# QCopterMV_MCU_Sch.net
KiCad netlist of a schematic drawn in Altium Designer
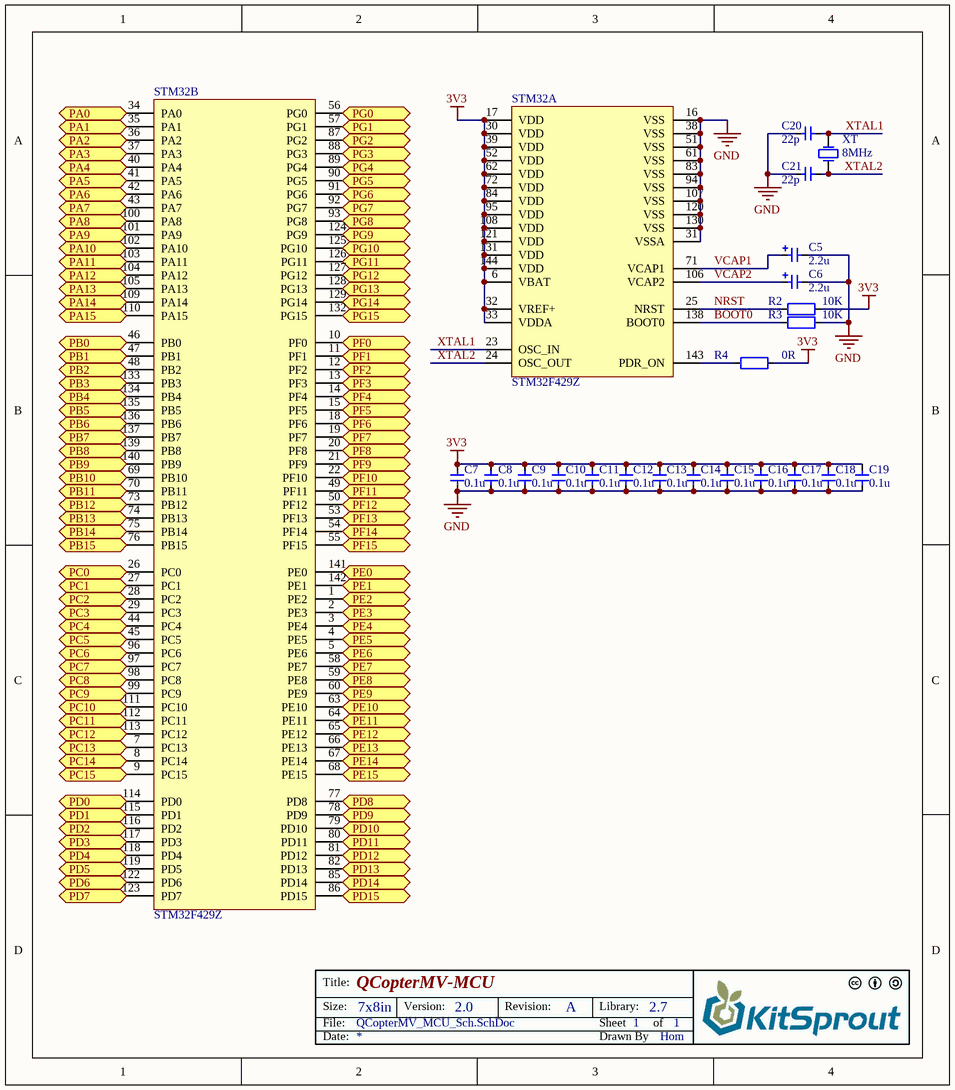
[diagram p0: QCopterMV_MCU_Sch.SchDoc]

(export (version "E")
  (design (tool "Eeschema 10.0.6"))
  (components
    (comp (ref "C5")
      (value "2.2u")
      (footprint "PCB_PassiveCap:CAP_TAN_P0805")
      (description "Capacitor")
      (fields (field (name "Comment") "Cap_Tan_0805"))
      (libsource (lib "SCH_Passive") (part "Cap_Tan_0805"))
    )
    (comp (ref "C6")
      (value "2.2u")
      (footprint "PCB_PassiveCap:CAP_TAN_P0805")
      (description "Capacitor")
      (fields (field (name "Comment") "Cap_Tan_0805"))
      (libsource (lib "SCH_Passive") (part "Cap_Tan_0805"))
    )
    (comp (ref "C7")
      (value "0.1u")
      (footprint "PCB_PassiveCap:CAP_0402")
      (description "Capacitor")
      (fields (field (name "Comment") "Cap_0402"))
      (libsource (lib "SCH_Passive") (part "Cap_0402"))
    )
    (comp (ref "C8")
      (value "0.1u")
      (footprint "PCB_PassiveCap:CAP_0402")
      (description "Capacitor")
      (fields (field (name "Comment") "Cap_0402"))
      (libsource (lib "SCH_Passive") (part "Cap_0402"))
    )
    (comp (ref "C9")
      (value "0.1u")
      (footprint "PCB_PassiveCap:CAP_0402")
      (description "Capacitor")
      (fields (field (name "Comment") "Cap_0402"))
      (libsource (lib "SCH_Passive") (part "Cap_0402"))
    )
    (comp (ref "C10")
      (value "0.1u")
      (footprint "PCB_PassiveCap:CAP_0402")
      (description "Capacitor")
      (fields (field (name "Comment") "Cap_0402"))
      (libsource (lib "SCH_Passive") (part "Cap_0402"))
    )
    (comp (ref "C11")
      (value "0.1u")
      (footprint "PCB_PassiveCap:CAP_0402")
      (description "Capacitor")
      (fields (field (name "Comment") "Cap_0402"))
      (libsource (lib "SCH_Passive") (part "Cap_0402"))
    )
    (comp (ref "C12")
      (value "0.1u")
      (footprint "PCB_PassiveCap:CAP_0402")
      (description "Capacitor")
      (fields (field (name "Comment") "Cap_0402"))
      (libsource (lib "SCH_Passive") (part "Cap_0402"))
    )
    (comp (ref "C13")
      (value "0.1u")
      (footprint "PCB_PassiveCap:CAP_0402")
      (description "Capacitor")
      (fields (field (name "Comment") "Cap_0402"))
      (libsource (lib "SCH_Passive") (part "Cap_0402"))
    )
    (comp (ref "C14")
      (value "0.1u")
      (footprint "PCB_PassiveCap:CAP_0402")
      (description "Capacitor")
      (fields (field (name "Comment") "Cap_0402"))
      (libsource (lib "SCH_Passive") (part "Cap_0402"))
    )
    (comp (ref "C15")
      (value "0.1u")
      (footprint "PCB_PassiveCap:CAP_0402")
      (description "Capacitor")
      (fields (field (name "Comment") "Cap_0402"))
      (libsource (lib "SCH_Passive") (part "Cap_0402"))
    )
    (comp (ref "C16")
      (value "0.1u")
      (footprint "PCB_PassiveCap:CAP_0402")
      (description "Capacitor")
      (fields (field (name "Comment") "Cap_0402"))
      (libsource (lib "SCH_Passive") (part "Cap_0402"))
    )
    (comp (ref "C17")
      (value "0.1u")
      (footprint "PCB_PassiveCap:CAP_0402")
      (description "Capacitor")
      (fields (field (name "Comment") "Cap_0402"))
      (libsource (lib "SCH_Passive") (part "Cap_0402"))
    )
    (comp (ref "C18")
      (value "0.1u")
      (footprint "PCB_PassiveCap:CAP_0402")
      (description "Capacitor")
      (fields (field (name "Comment") "Cap_0402"))
      (libsource (lib "SCH_Passive") (part "Cap_0402"))
    )
    (comp (ref "C19")
      (value "0.1u")
      (footprint "PCB_PassiveCap:CAP_0402")
      (description "Capacitor")
      (fields (field (name "Comment") "Cap_0402"))
      (libsource (lib "SCH_Passive") (part "Cap_0402"))
    )
    (comp (ref "C20")
      (value "22p")
      (footprint "PCB_PassiveCap:CAP_0402")
      (description "Capacitor")
      (fields (field (name "Comment") "Cap_0402"))
      (libsource (lib "SCH_Passive") (part "Cap_0402"))
    )
    (comp (ref "C21")
      (value "22p")
      (footprint "PCB_PassiveCap:CAP_0402")
      (description "Capacitor")
      (fields (field (name "Comment") "Cap_0402"))
      (libsource (lib "SCH_Passive") (part "Cap_0402"))
    )
    (comp (ref "R2")
      (value "10K")
      (footprint "PCB_PassiveRes:RES_0402")
      (description "Resistor")
      (fields (field (name "Comment") "Res_0402"))
      (libsource (lib "SCH_Passive") (part "Res_0402"))
    )
    (comp (ref "R3")
      (value "10K")
      (footprint "PCB_PassiveRes:RES_0402")
      (description "Resistor")
      (fields (field (name "Comment") "Res_0402"))
      (libsource (lib "SCH_Passive") (part "Res_0402"))
    )
    (comp (ref "R4")
      (value "0R")
      (footprint "PCB_PassiveRes:RES_0402")
      (description "Resistor")
      (fields (field (name "Comment") "Res_0402"))
      (libsource (lib "SCH_Passive") (part "Res_0402"))
    )
    (comp (ref "STM32")
      (value "STM32F429Z")
      (footprint "PCB_IntegratedCircuit:LQFP_P0.5_144")
      (description "MCU")
      (libsource (lib "SCH_IntegratedCircuit") (part "STM32F439Z"))
    )
    (comp (ref "XT")
      (value "8MHz")
      (footprint "PCB_Oscillator:XT_3225_2")
      (description "Crystal Oscillator")
      (fields (field (name "Comment") "XTAL_3225_2P"))
      (libsource (lib "SCH_Oscillator") (part "XTAL_3225_2P"))
    )
  )
  (nets
    (net (code "1") (name "/BOOT0") (class "Default")
      (node (ref "R3") (pin "2") (pinfunction "2_2") (pintype "passive"))
      (node (ref "STM32") (pin "138") (pinfunction "BOOT0_138") (pintype "passive"))
    )
    (net (code "2") (name "/NRST") (class "Default")
      (node (ref "R2") (pin "2") (pinfunction "2_2") (pintype "passive"))
      (node (ref "STM32") (pin "25") (pinfunction "NRST_25") (pintype "passive"))
    )
    (net (code "3") (name "/PA0") (class "Default")
      (node (ref "STM32") (pin "34") (pinfunction "PA0_34") (pintype "passive"))
    )
    (net (code "4") (name "/PA1") (class "Default")
      (node (ref "STM32") (pin "35") (pinfunction "PA1_35") (pintype "passive"))
    )
    (net (code "5") (name "/PA2") (class "Default")
      (node (ref "STM32") (pin "36") (pinfunction "PA2_36") (pintype "passive"))
    )
    (net (code "6") (name "/PA3") (class "Default")
      (node (ref "STM32") (pin "37") (pinfunction "PA3_37") (pintype "passive"))
    )
    (net (code "7") (name "/PA4") (class "Default")
      (node (ref "STM32") (pin "40") (pinfunction "PA4_40") (pintype "passive"))
    )
    (net (code "8") (name "/PA5") (class "Default")
      (node (ref "STM32") (pin "41") (pinfunction "PA5_41") (pintype "passive"))
    )
    (net (code "9") (name "/PA6") (class "Default")
      (node (ref "STM32") (pin "42") (pinfunction "PA6_42") (pintype "passive"))
    )
    (net (code "10") (name "/PA7") (class "Default")
      (node (ref "STM32") (pin "43") (pinfunction "PA7_43") (pintype "passive"))
    )
    (net (code "11") (name "/PA8") (class "Default")
      (node (ref "STM32") (pin "100") (pinfunction "PA8_100") (pintype "passive"))
    )
    (net (code "12") (name "/PA9") (class "Default")
      (node (ref "STM32") (pin "101") (pinfunction "PA9_101") (pintype "passive"))
    )
    (net (code "13") (name "/PA10") (class "Default")
      (node (ref "STM32") (pin "102") (pinfunction "PA10_102") (pintype "passive"))
    )
    (net (code "14") (name "/PA11") (class "Default")
      (node (ref "STM32") (pin "103") (pinfunction "PA11_103") (pintype "passive"))
    )
    (net (code "15") (name "/PA12") (class "Default")
      (node (ref "STM32") (pin "104") (pinfunction "PA12_104") (pintype "passive"))
    )
    (net (code "16") (name "/PA13") (class "Default")
      (node (ref "STM32") (pin "105") (pinfunction "PA13_105") (pintype "passive"))
    )
    (net (code "17") (name "/PA14") (class "Default")
      (node (ref "STM32") (pin "109") (pinfunction "PA14_109") (pintype "passive"))
    )
    (net (code "18") (name "/PA15") (class "Default")
      (node (ref "STM32") (pin "110") (pinfunction "PA15_110") (pintype "passive"))
    )
    (net (code "19") (name "/PB0") (class "Default")
      (node (ref "STM32") (pin "46") (pinfunction "PB0_46") (pintype "passive"))
    )
    (net (code "20") (name "/PB1") (class "Default")
      (node (ref "STM32") (pin "47") (pinfunction "PB1_47") (pintype "passive"))
    )
    (net (code "21") (name "/PB2") (class "Default")
      (node (ref "STM32") (pin "48") (pinfunction "PB2_48") (pintype "passive"))
    )
    (net (code "22") (name "/PB3") (class "Default")
      (node (ref "STM32") (pin "133") (pinfunction "PB3_133") (pintype "passive"))
    )
    (net (code "23") (name "/PB4") (class "Default")
      (node (ref "STM32") (pin "134") (pinfunction "PB4_134") (pintype "passive"))
    )
    (net (code "24") (name "/PB5") (class "Default")
      (node (ref "STM32") (pin "135") (pinfunction "PB5_135") (pintype "passive"))
    )
    (net (code "25") (name "/PB6") (class "Default")
      (node (ref "STM32") (pin "136") (pinfunction "PB6_136") (pintype "passive"))
    )
    (net (code "26") (name "/PB7") (class "Default")
      (node (ref "STM32") (pin "137") (pinfunction "PB7_137") (pintype "passive"))
    )
    (net (code "27") (name "/PB8") (class "Default")
      (node (ref "STM32") (pin "139") (pinfunction "PB8_139") (pintype "passive"))
    )
    (net (code "28") (name "/PB9") (class "Default")
      (node (ref "STM32") (pin "140") (pinfunction "PB9_140") (pintype "passive"))
    )
    (net (code "29") (name "/PB10") (class "Default")
      (node (ref "STM32") (pin "69") (pinfunction "PB10_69") (pintype "passive"))
    )
    (net (code "30") (name "/PB11") (class "Default")
      (node (ref "STM32") (pin "70") (pinfunction "PB11_70") (pintype "passive"))
    )
    (net (code "31") (name "/PB12") (class "Default")
      (node (ref "STM32") (pin "73") (pinfunction "PB12_73") (pintype "passive"))
    )
    (net (code "32") (name "/PB13") (class "Default")
      (node (ref "STM32") (pin "74") (pinfunction "PB13_74") (pintype "passive"))
    )
    (net (code "33") (name "/PB14") (class "Default")
      (node (ref "STM32") (pin "75") (pinfunction "PB14_75") (pintype "passive"))
    )
    (net (code "34") (name "/PB15") (class "Default")
      (node (ref "STM32") (pin "76") (pinfunction "PB15_76") (pintype "passive"))
    )
    (net (code "35") (name "/PC0") (class "Default")
      (node (ref "STM32") (pin "26") (pinfunction "PC0_26") (pintype "passive"))
    )
    (net (code "36") (name "/PC1") (class "Default")
      (node (ref "STM32") (pin "27") (pinfunction "PC1_27") (pintype "passive"))
    )
    (net (code "37") (name "/PC2") (class "Default")
      (node (ref "STM32") (pin "28") (pinfunction "PC2_28") (pintype "passive"))
    )
    (net (code "38") (name "/PC3") (class "Default")
      (node (ref "STM32") (pin "29") (pinfunction "PC3_29") (pintype "passive"))
    )
    (net (code "39") (name "/PC4") (class "Default")
      (node (ref "STM32") (pin "44") (pinfunction "PC4_44") (pintype "passive"))
    )
    (net (code "40") (name "/PC5") (class "Default")
      (node (ref "STM32") (pin "45") (pinfunction "PC5_45") (pintype "passive"))
    )
    (net (code "41") (name "/PC6") (class "Default")
      (node (ref "STM32") (pin "96") (pinfunction "PC6_96") (pintype "passive"))
    )
    (net (code "42") (name "/PC7") (class "Default")
      (node (ref "STM32") (pin "97") (pinfunction "PC7_97") (pintype "passive"))
    )
    (net (code "43") (name "/PC8") (class "Default")
      (node (ref "STM32") (pin "98") (pinfunction "PC8_98") (pintype "passive"))
    )
    (net (code "44") (name "/PC9") (class "Default")
      (node (ref "STM32") (pin "99") (pinfunction "PC9_99") (pintype "passive"))
    )
    (net (code "45") (name "/PC10") (class "Default")
      (node (ref "STM32") (pin "111") (pinfunction "PC10_111") (pintype "passive"))
    )
    (net (code "46") (name "/PC11") (class "Default")
      (node (ref "STM32") (pin "112") (pinfunction "PC11_112") (pintype "passive"))
    )
    (net (code "47") (name "/PC12") (class "Default")
      (node (ref "STM32") (pin "113") (pinfunction "PC12_113") (pintype "passive"))
    )
    (net (code "48") (name "/PC13") (class "Default")
      (node (ref "STM32") (pin "7") (pinfunction "PC13_7") (pintype "passive"))
    )
    (net (code "49") (name "/PC14") (class "Default")
      (node (ref "STM32") (pin "8") (pinfunction "PC14_8") (pintype "passive"))
    )
    (net (code "50") (name "/PC15") (class "Default")
      (node (ref "STM32") (pin "9") (pinfunction "PC15_9") (pintype "passive"))
    )
    (net (code "51") (name "/PD0") (class "Default")
      (node (ref "STM32") (pin "114") (pinfunction "PD0_114") (pintype "passive"))
    )
    (net (code "52") (name "/PD1") (class "Default")
      (node (ref "STM32") (pin "115") (pinfunction "PD1_115") (pintype "passive"))
    )
    (net (code "53") (name "/PD2") (class "Default")
      (node (ref "STM32") (pin "116") (pinfunction "PD2_116") (pintype "passive"))
    )
    (net (code "54") (name "/PD3") (class "Default")
      (node (ref "STM32") (pin "117") (pinfunction "PD3_117") (pintype "passive"))
    )
    (net (code "55") (name "/PD4") (class "Default")
      (node (ref "STM32") (pin "118") (pinfunction "PD4_118") (pintype "passive"))
    )
    (net (code "56") (name "/PD5") (class "Default")
      (node (ref "STM32") (pin "119") (pinfunction "PD5_119") (pintype "passive"))
    )
    (net (code "57") (name "/PD6") (class "Default")
      (node (ref "STM32") (pin "122") (pinfunction "PD6_122") (pintype "passive"))
    )
    (net (code "58") (name "/PD7") (class "Default")
      (node (ref "STM32") (pin "123") (pinfunction "PD7_123") (pintype "passive"))
    )
    (net (code "59") (name "/PD8") (class "Default")
      (node (ref "STM32") (pin "77") (pinfunction "PD8_77") (pintype "passive"))
    )
    (net (code "60") (name "/PD9") (class "Default")
      (node (ref "STM32") (pin "78") (pinfunction "PD9_78") (pintype "passive"))
    )
    (net (code "61") (name "/PD10") (class "Default")
      (node (ref "STM32") (pin "79") (pinfunction "PD10_79") (pintype "passive"))
    )
    (net (code "62") (name "/PD11") (class "Default")
      (node (ref "STM32") (pin "80") (pinfunction "PD11_80") (pintype "passive"))
    )
    (net (code "63") (name "/PD12") (class "Default")
      (node (ref "STM32") (pin "81") (pinfunction "PD12_81") (pintype "passive"))
    )
    (net (code "64") (name "/PD13") (class "Default")
      (node (ref "STM32") (pin "82") (pinfunction "PD13_82") (pintype "passive"))
    )
    (net (code "65") (name "/PD14") (class "Default")
      (node (ref "STM32") (pin "85") (pinfunction "PD14_85") (pintype "passive"))
    )
    (net (code "66") (name "/PD15") (class "Default")
      (node (ref "STM32") (pin "86") (pinfunction "PD15_86") (pintype "passive"))
    )
    (net (code "67") (name "/PE0") (class "Default")
      (node (ref "STM32") (pin "141") (pinfunction "PE0_141") (pintype "passive"))
    )
    (net (code "68") (name "/PE1") (class "Default")
      (node (ref "STM32") (pin "142") (pinfunction "PE1_142") (pintype "passive"))
    )
    (net (code "69") (name "/PE2") (class "Default")
      (node (ref "STM32") (pin "1") (pinfunction "PE2_1") (pintype "passive"))
    )
    (net (code "70") (name "/PE3") (class "Default")
      (node (ref "STM32") (pin "2") (pinfunction "PE3_2") (pintype "passive"))
    )
    (net (code "71") (name "/PE4") (class "Default")
      (node (ref "STM32") (pin "3") (pinfunction "PE4_3") (pintype "passive"))
    )
    (net (code "72") (name "/PE5") (class "Default")
      (node (ref "STM32") (pin "4") (pinfunction "PE5_4") (pintype "passive"))
    )
    (net (code "73") (name "/PE6") (class "Default")
      (node (ref "STM32") (pin "5") (pinfunction "PE6_5") (pintype "passive"))
    )
    (net (code "74") (name "/PE7") (class "Default")
      (node (ref "STM32") (pin "58") (pinfunction "PE7_58") (pintype "passive"))
    )
    (net (code "75") (name "/PE8") (class "Default")
      (node (ref "STM32") (pin "59") (pinfunction "PE8_59") (pintype "passive"))
    )
    (net (code "76") (name "/PE9") (class "Default")
      (node (ref "STM32") (pin "60") (pinfunction "PE9_60") (pintype "passive"))
    )
    (net (code "77") (name "/PE10") (class "Default")
      (node (ref "STM32") (pin "63") (pinfunction "PE10_63") (pintype "passive"))
    )
    (net (code "78") (name "/PE11") (class "Default")
      (node (ref "STM32") (pin "64") (pinfunction "PE11_64") (pintype "passive"))
    )
    (net (code "79") (name "/PE12") (class "Default")
      (node (ref "STM32") (pin "65") (pinfunction "PE12_65") (pintype "passive"))
    )
    (net (code "80") (name "/PE13") (class "Default")
      (node (ref "STM32") (pin "66") (pinfunction "PE13_66") (pintype "passive"))
    )
    (net (code "81") (name "/PE14") (class "Default")
      (node (ref "STM32") (pin "67") (pinfunction "PE14_67") (pintype "passive"))
    )
    (net (code "82") (name "/PE15") (class "Default")
      (node (ref "STM32") (pin "68") (pinfunction "PE15_68") (pintype "passive"))
    )
    (net (code "83") (name "/PF0") (class "Default")
      (node (ref "STM32") (pin "10") (pinfunction "PF0_10") (pintype "passive"))
    )
    (net (code "84") (name "/PF1") (class "Default")
      (node (ref "STM32") (pin "11") (pinfunction "PF1_11") (pintype "passive"))
    )
    (net (code "85") (name "/PF2") (class "Default")
      (node (ref "STM32") (pin "12") (pinfunction "PF2_12") (pintype "passive"))
    )
    (net (code "86") (name "/PF3") (class "Default")
      (node (ref "STM32") (pin "13") (pinfunction "PF3_13") (pintype "passive"))
    )
    (net (code "87") (name "/PF4") (class "Default")
      (node (ref "STM32") (pin "14") (pinfunction "PF4_14") (pintype "passive"))
    )
    (net (code "88") (name "/PF5") (class "Default")
      (node (ref "STM32") (pin "15") (pinfunction "PF5_15") (pintype "passive"))
    )
    (net (code "89") (name "/PF6") (class "Default")
      (node (ref "STM32") (pin "18") (pinfunction "PF6_18") (pintype "passive"))
    )
    (net (code "90") (name "/PF7") (class "Default")
      (node (ref "STM32") (pin "19") (pinfunction "PF7_19") (pintype "passive"))
    )
    (net (code "91") (name "/PF8") (class "Default")
      (node (ref "STM32") (pin "20") (pinfunction "PF8_20") (pintype "passive"))
    )
    (net (code "92") (name "/PF9") (class "Default")
      (node (ref "STM32") (pin "21") (pinfunction "PF9_21") (pintype "passive"))
    )
    (net (code "93") (name "/PF10") (class "Default")
      (node (ref "STM32") (pin "22") (pinfunction "PF10_22") (pintype "passive"))
    )
    (net (code "94") (name "/PF11") (class "Default")
      (node (ref "STM32") (pin "49") (pinfunction "PF11_49") (pintype "passive"))
    )
    (net (code "95") (name "/PF12") (class "Default")
      (node (ref "STM32") (pin "50") (pinfunction "PF12_50") (pintype "passive"))
    )
    (net (code "96") (name "/PF13") (class "Default")
      (node (ref "STM32") (pin "53") (pinfunction "PF13_53") (pintype "passive"))
    )
    (net (code "97") (name "/PF14") (class "Default")
      (node (ref "STM32") (pin "54") (pinfunction "PF14_54") (pintype "passive"))
    )
    (net (code "98") (name "/PF15") (class "Default")
      (node (ref "STM32") (pin "55") (pinfunction "PF15_55") (pintype "passive"))
    )
    (net (code "99") (name "/PG0") (class "Default")
      (node (ref "STM32") (pin "56") (pinfunction "PG0_56") (pintype "passive"))
    )
    (net (code "100") (name "/PG1") (class "Default")
      (node (ref "STM32") (pin "57") (pinfunction "PG1_57") (pintype "passive"))
    )
    (net (code "101") (name "/PG2") (class "Default")
      (node (ref "STM32") (pin "87") (pinfunction "PG2_87") (pintype "passive"))
    )
    (net (code "102") (name "/PG3") (class "Default")
      (node (ref "STM32") (pin "88") (pinfunction "PG3_88") (pintype "passive"))
    )
    (net (code "103") (name "/PG4") (class "Default")
      (node (ref "STM32") (pin "89") (pinfunction "PG4_89") (pintype "passive"))
    )
    (net (code "104") (name "/PG5") (class "Default")
      (node (ref "STM32") (pin "90") (pinfunction "PG5_90") (pintype "passive"))
    )
    (net (code "105") (name "/PG6") (class "Default")
      (node (ref "STM32") (pin "91") (pinfunction "PG6_91") (pintype "passive"))
    )
    (net (code "106") (name "/PG7") (class "Default")
      (node (ref "STM32") (pin "92") (pinfunction "PG7_92") (pintype "passive"))
    )
    (net (code "107") (name "/PG8") (class "Default")
      (node (ref "STM32") (pin "93") (pinfunction "PG8_93") (pintype "passive"))
    )
    (net (code "108") (name "/PG9") (class "Default")
      (node (ref "STM32") (pin "124") (pinfunction "PG9_124") (pintype "passive"))
    )
    (net (code "109") (name "/PG10") (class "Default")
      (node (ref "STM32") (pin "125") (pinfunction "PG10_125") (pintype "passive"))
    )
    (net (code "110") (name "/PG11") (class "Default")
      (node (ref "STM32") (pin "126") (pinfunction "PG11_126") (pintype "passive"))
    )
    (net (code "111") (name "/PG12") (class "Default")
      (node (ref "STM32") (pin "127") (pinfunction "PG12_127") (pintype "passive"))
    )
    (net (code "112") (name "/PG13") (class "Default")
      (node (ref "STM32") (pin "128") (pinfunction "PG13_128") (pintype "passive"))
    )
    (net (code "113") (name "/PG14") (class "Default")
      (node (ref "STM32") (pin "129") (pinfunction "PG14_129") (pintype "passive"))
    )
    (net (code "114") (name "/PG15") (class "Default")
      (node (ref "STM32") (pin "132") (pinfunction "PG15_132") (pintype "passive"))
    )
    (net (code "115") (name "/VCAP1") (class "Default")
      (node (ref "C5") (pin "1") (pinfunction "1_1") (pintype "passive"))
      (node (ref "STM32") (pin "71") (pinfunction "VCAP1_71") (pintype "passive"))
    )
    (net (code "116") (name "/VCAP2") (class "Default")
      (node (ref "C6") (pin "1") (pinfunction "1_1") (pintype "passive"))
      (node (ref "STM32") (pin "106") (pinfunction "VCAP2_106") (pintype "passive"))
    )
    (net (code "117") (name "/XTAL1") (class "Default")
      (node (ref "C20") (pin "2") (pinfunction "2_2") (pintype "passive"))
      (node (ref "STM32") (pin "23") (pinfunction "OSC_IN_23") (pintype "passive"))
      (node (ref "XT") (pin "2") (pinfunction "OSC2_2") (pintype "passive"))
    )
    (net (code "118") (name "/XTAL2") (class "Default")
      (node (ref "C21") (pin "2") (pinfunction "2_2") (pintype "passive"))
      (node (ref "STM32") (pin "24") (pinfunction "OSC_OUT_24") (pintype "passive"))
      (node (ref "XT") (pin "1") (pinfunction "OSC1_1") (pintype "passive"))
    )
    (net (code "119") (name "3V3") (class "Default")
      (node (ref "C10") (pin "2") (pinfunction "2_2") (pintype "passive"))
      (node (ref "C11") (pin "2") (pinfunction "2_2") (pintype "passive"))
      (node (ref "C12") (pin "2") (pinfunction "2_2") (pintype "passive"))
      (node (ref "C13") (pin "2") (pinfunction "2_2") (pintype "passive"))
      (node (ref "C14") (pin "2") (pinfunction "2_2") (pintype "passive"))
      (node (ref "C15") (pin "2") (pinfunction "2_2") (pintype "passive"))
      (node (ref "C16") (pin "2") (pinfunction "2_2") (pintype "passive"))
      (node (ref "C17") (pin "2") (pinfunction "2_2") (pintype "passive"))
      (node (ref "C18") (pin "2") (pinfunction "2_2") (pintype "passive"))
      (node (ref "C19") (pin "2") (pinfunction "2_2") (pintype "passive"))
      (node (ref "C7") (pin "2") (pinfunction "2_2") (pintype "passive"))
      (node (ref "C8") (pin "2") (pinfunction "2_2") (pintype "passive"))
      (node (ref "C9") (pin "2") (pinfunction "2_2") (pintype "passive"))
      (node (ref "R2") (pin "1") (pinfunction "1_1") (pintype "passive"))
      (node (ref "R4") (pin "1") (pinfunction "1_1") (pintype "passive"))
      (node (ref "STM32") (pin "108") (pinfunction "VDD_108") (pintype "passive"))
      (node (ref "STM32") (pin "121") (pinfunction "VDD_121") (pintype "passive"))
      (node (ref "STM32") (pin "131") (pinfunction "VDD_131") (pintype "passive"))
      (node (ref "STM32") (pin "144") (pinfunction "VDD_144") (pintype "passive"))
      (node (ref "STM32") (pin "17") (pinfunction "VDD_17") (pintype "passive"))
      (node (ref "STM32") (pin "30") (pinfunction "VDD_30") (pintype "passive"))
      (node (ref "STM32") (pin "32") (pinfunction "VREF+_32") (pintype "passive"))
      (node (ref "STM32") (pin "33") (pinfunction "VDDA_33") (pintype "passive"))
      (node (ref "STM32") (pin "39") (pinfunction "VDD_39") (pintype "passive"))
      (node (ref "STM32") (pin "52") (pinfunction "VDD_52") (pintype "passive"))
      (node (ref "STM32") (pin "6") (pinfunction "VBAT_6") (pintype "passive"))
      (node (ref "STM32") (pin "62") (pinfunction "VDD_62") (pintype "passive"))
      (node (ref "STM32") (pin "72") (pinfunction "VDD_72") (pintype "passive"))
      (node (ref "STM32") (pin "84") (pinfunction "VDD_84") (pintype "passive"))
      (node (ref "STM32") (pin "95") (pinfunction "VDD_95") (pintype "passive"))
    )
    (net (code "120") (name "GND") (class "Default")
      (node (ref "C10") (pin "1") (pinfunction "1_1") (pintype "passive"))
      (node (ref "C11") (pin "1") (pinfunction "1_1") (pintype "passive"))
      (node (ref "C12") (pin "1") (pinfunction "1_1") (pintype "passive"))
      (node (ref "C13") (pin "1") (pinfunction "1_1") (pintype "passive"))
      (node (ref "C14") (pin "1") (pinfunction "1_1") (pintype "passive"))
      (node (ref "C15") (pin "1") (pinfunction "1_1") (pintype "passive"))
      (node (ref "C16") (pin "1") (pinfunction "1_1") (pintype "passive"))
      (node (ref "C17") (pin "1") (pinfunction "1_1") (pintype "passive"))
      (node (ref "C18") (pin "1") (pinfunction "1_1") (pintype "passive"))
      (node (ref "C19") (pin "1") (pinfunction "1_1") (pintype "passive"))
      (node (ref "C20") (pin "1") (pinfunction "1_1") (pintype "passive"))
      (node (ref "C21") (pin "1") (pinfunction "1_1") (pintype "passive"))
      (node (ref "C5") (pin "2") (pinfunction "2_2") (pintype "passive"))
      (node (ref "C6") (pin "2") (pinfunction "2_2") (pintype "passive"))
      (node (ref "C7") (pin "1") (pinfunction "1_1") (pintype "passive"))
      (node (ref "C8") (pin "1") (pinfunction "1_1") (pintype "passive"))
      (node (ref "C9") (pin "1") (pinfunction "1_1") (pintype "passive"))
      (node (ref "R3") (pin "1") (pinfunction "1_1") (pintype "passive"))
      (node (ref "STM32") (pin "107") (pinfunction "VSS_107") (pintype "passive"))
      (node (ref "STM32") (pin "120") (pinfunction "VSS_120") (pintype "passive"))
      (node (ref "STM32") (pin "130") (pinfunction "VSS_130") (pintype "passive"))
      (node (ref "STM32") (pin "16") (pinfunction "VSS_16") (pintype "passive"))
      (node (ref "STM32") (pin "31") (pinfunction "VSSA_31") (pintype "passive"))
      (node (ref "STM32") (pin "38") (pinfunction "VSS_38") (pintype "passive"))
      (node (ref "STM32") (pin "51") (pinfunction "VSS_51") (pintype "passive"))
      (node (ref "STM32") (pin "61") (pinfunction "VSS_61") (pintype "passive"))
      (node (ref "STM32") (pin "83") (pinfunction "VSS_83") (pintype "passive"))
      (node (ref "STM32") (pin "94") (pinfunction "VSS_94") (pintype "passive"))
    )
    (net (code "121") (name "Net-(STM32A-PDR_ON)") (class "Default")
      (node (ref "R4") (pin "2") (pinfunction "2_2") (pintype "passive"))
      (node (ref "STM32") (pin "143") (pinfunction "PDR_ON_143") (pintype "passive"))
    )
  )
)
